# CAN1.net
KiCad netlist of a schematic drawn in Altium Designer
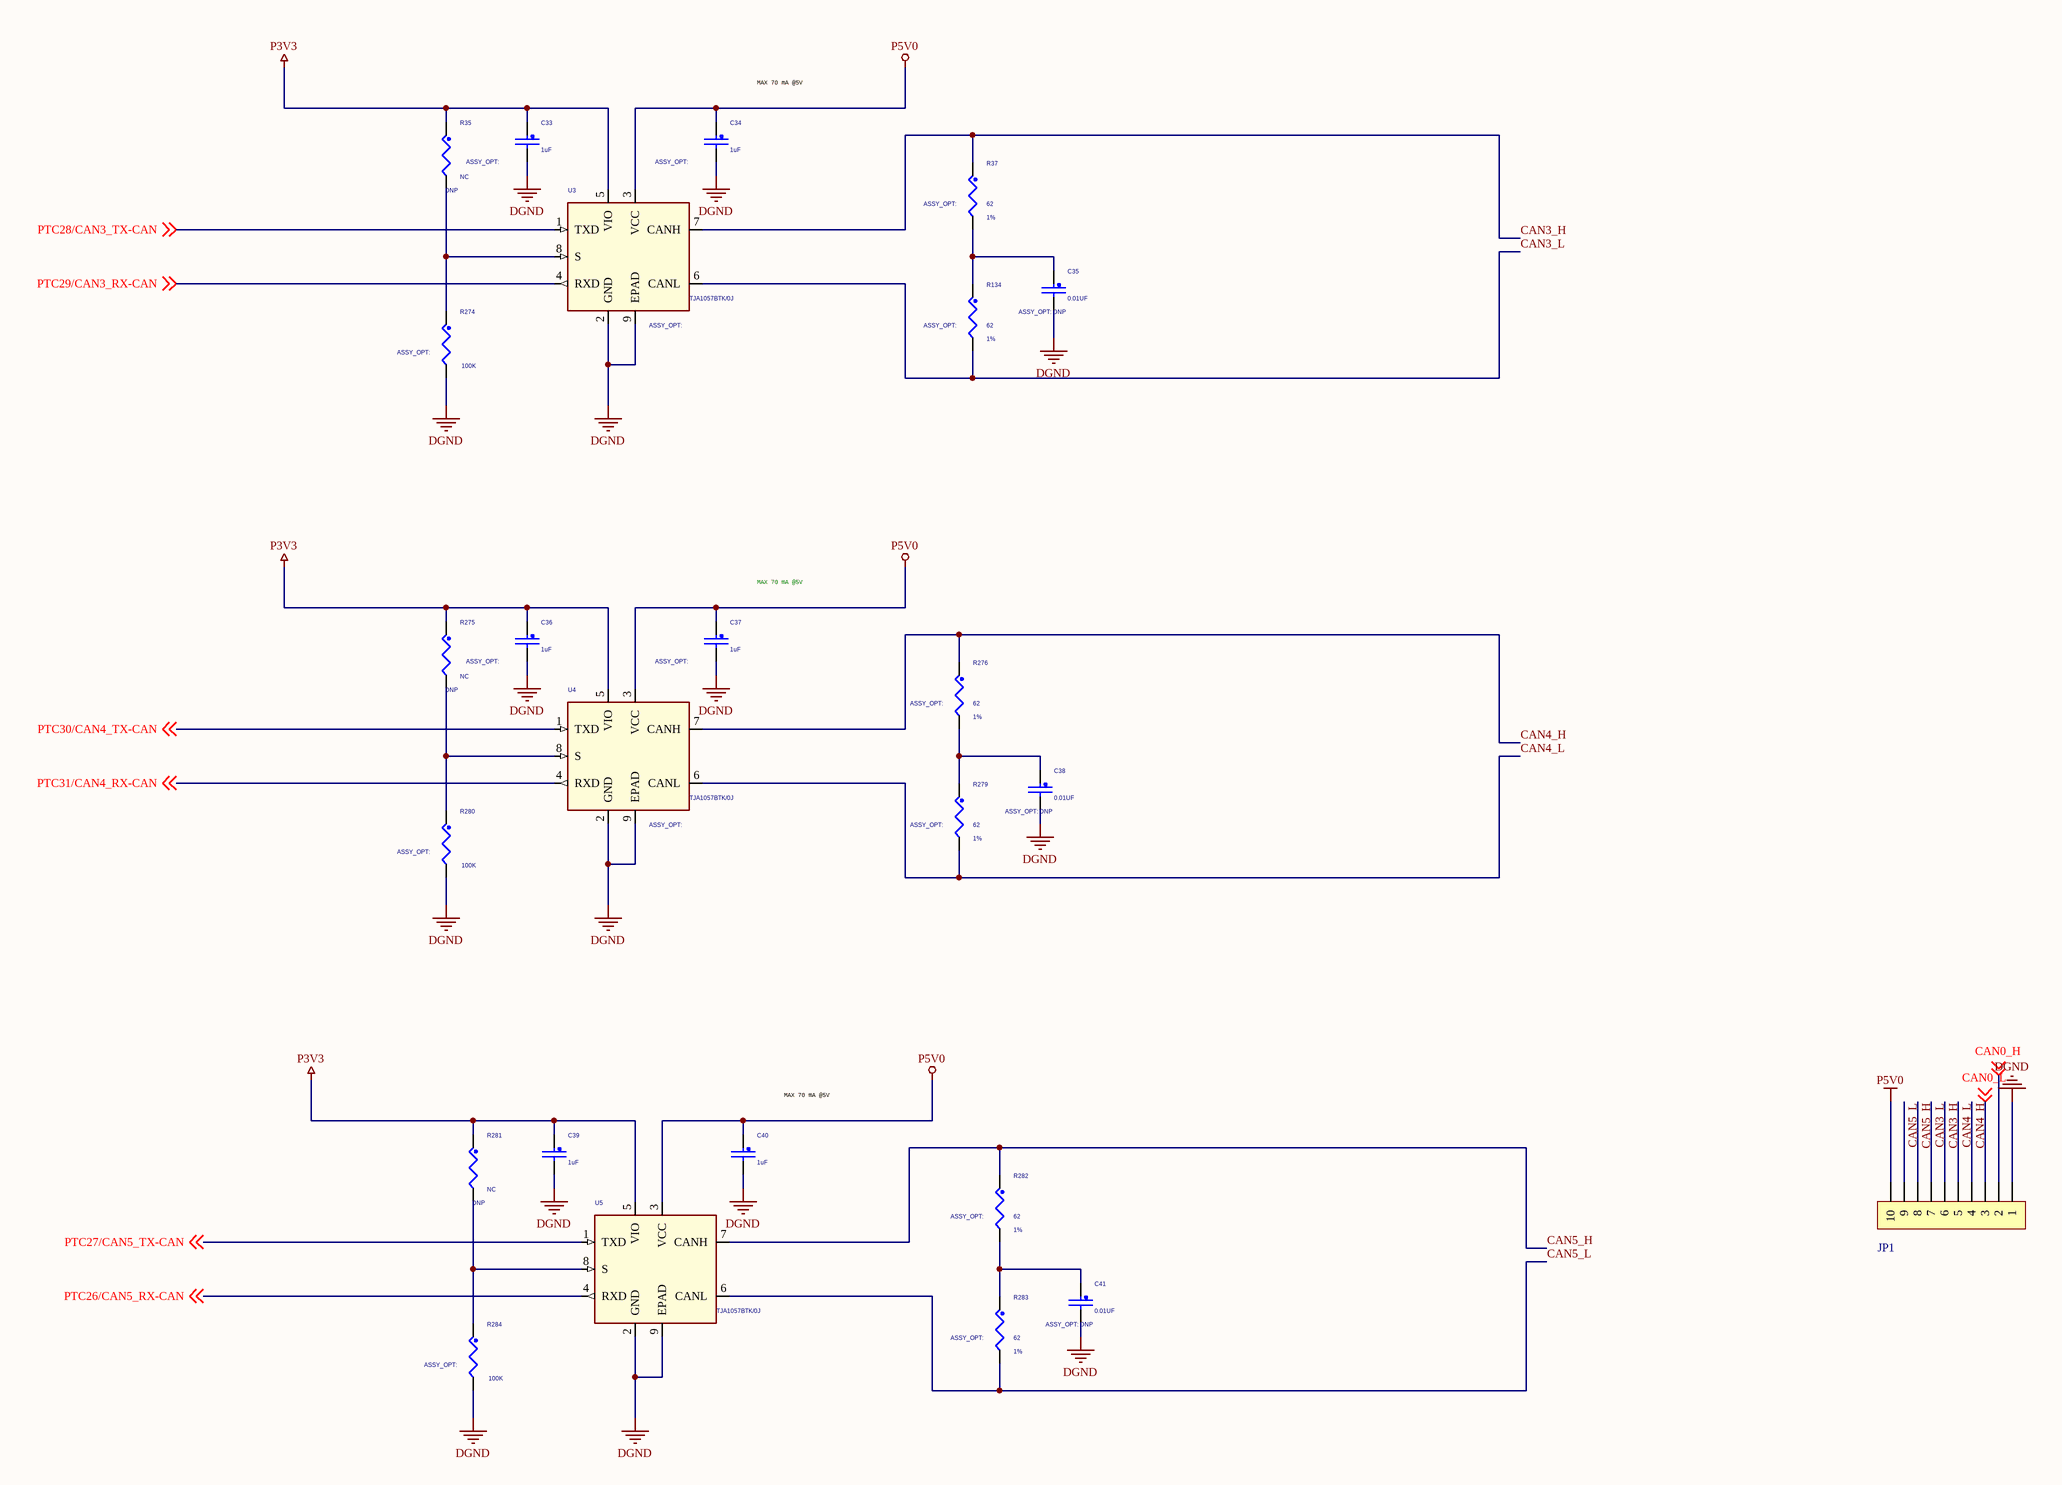
[diagram p0: CAN1.SchDoc]

(export (version "E")
  (design (tool "Eeschema 10.0.6"))
  (components
    (comp (ref "C33")
      (value "1uF")
      (footprint "CC0402_25")
      (description "CAP CER 1.0uF 16V 10% X6S 0402")
      (fields (field (name "VOLTAGE") "16V") (field (name "TOLERANCE") "10%"))
      (libsource (lib "*") (part "CAP_NP"))
    )
    (comp (ref "C34")
      (value "1uF")
      (footprint "CC0402_25")
      (description "CAP CER 1.0uF 16V 10% X6S 0402")
      (fields (field (name "VOLTAGE") "16V") (field (name "TOLERANCE") "10%"))
      (libsource (lib "*") (part "CAP_NP"))
    )
    (comp (ref "C35")
      (value "0.01UF")
      (footprint "CC0402_25")
      (description "CAP CER 0.01UF 50V 10% X7R 0402")
      (fields (field (name "ASSY_OPT") "DNP") (field (name "TOLERANCE") "10%"))
      (libsource (lib "*") (part "CAP_NP"))
    )
    (comp (ref "C36")
      (value "1uF")
      (footprint "CC0402_25")
      (description "CAP CER 1.0uF 16V 10% X6S 0402")
      (fields (field (name "TOLERANCE") "10%") (field (name "VOLTAGE") "16V"))
      (libsource (lib "*") (part "CAP_NP"))
    )
    (comp (ref "C37")
      (value "1uF")
      (footprint "CC0402_25")
      (description "CAP CER 1.0uF 16V 10% X6S 0402")
      (fields (field (name "TOLERANCE") "10%") (field (name "VOLTAGE") "16V"))
      (libsource (lib "*") (part "CAP_NP"))
    )
    (comp (ref "C38")
      (value "0.01UF")
      (footprint "CC0402_25")
      (description "CAP CER 0.01UF 50V 10% X7R 0402")
      (fields (field (name "ASSY_OPT") "DNP") (field (name "TOLERANCE") "10%"))
      (libsource (lib "*") (part "CAP_NP"))
    )
    (comp (ref "C39")
      (value "1uF")
      (footprint "CC0402_25")
      (description "CAP CER 1.0uF 16V 10% X6S 0402")
      (fields (field (name "VOLTAGE") "16V") (field (name "TOLERANCE") "10%"))
      (libsource (lib "*") (part "CAP_NP"))
    )
    (comp (ref "C40")
      (value "1uF")
      (footprint "CC0402_25")
      (description "CAP CER 1.0uF 16V 10% X6S 0402")
      (fields (field (name "TOLERANCE") "10%") (field (name "VOLTAGE") "16V"))
      (libsource (lib "*") (part "CAP_NP"))
    )
    (comp (ref "C41")
      (value "0.01UF")
      (footprint "CC0402_25")
      (description "CAP CER 0.01UF 50V 10% X7R 0402")
      (fields (field (name "ASSY_OPT") "DNP") (field (name "TOLERANCE") "10%"))
      (libsource (lib "*") (part "CAP_NP"))
    )
    (comp (ref "JP1")
      (value "HDR-1X10")
      (footprint "KF128-3.81-10P")
      (description "10P接插件")
      (libsource (lib "4.8   - 接插件-脚距3.81") (part "Header 10"))
    )
    (comp (ref "R35")
      (value "NC")
      (footprint "RC0402_25")
      (description "RES MF 10K 1/16W 5% 0402")
      (fields (field (name "ASSY_OPT") "DNP") (field (name "TOLERANCE") "5%"))
      (libsource (lib "*") (part "RES"))
    )
    (comp (ref "R37")
      (value "62")
      (footprint "RC0805_OV")
      (description "RES MF 62 OHM 1/4W 1% AEC-Q200 0805")
      (fields (field (name "TOLERANCE") "1%"))
      (libsource (lib "*") (part "RES"))
    )
    (comp (ref "R134")
      (value "62")
      (footprint "RC0805_OV")
      (description "RES MF 62 OHM 1/4W 1% AEC-Q200 0805")
      (fields (field (name "TOLERANCE") "1%"))
      (libsource (lib "*") (part "RES"))
    )
    (comp (ref "R274")
      (value "100K")
      (footprint "RC0402_25")
      (description "RES MF 100K 1/16W 1% 0402")
      (fields (field (name "TOLERANCE") "1%"))
      (libsource (lib "*") (part "RES"))
    )
    (comp (ref "R275")
      (value "NC")
      (footprint "RC0402_25")
      (description "RES MF 10K 1/16W 5% 0402")
      (fields (field (name "ASSY_OPT") "DNP") (field (name "TOLERANCE") "5%"))
      (libsource (lib "*") (part "RES"))
    )
    (comp (ref "R276")
      (value "62")
      (footprint "RC0805_OV")
      (description "RES MF 62 OHM 1/4W 1% AEC-Q200 0805")
      (fields (field (name "TOLERANCE") "1%"))
      (libsource (lib "*") (part "RES"))
    )
    (comp (ref "R279")
      (value "62")
      (footprint "RC0805_OV")
      (description "RES MF 62 OHM 1/4W 1% AEC-Q200 0805")
      (fields (field (name "TOLERANCE") "1%"))
      (libsource (lib "*") (part "RES"))
    )
    (comp (ref "R280")
      (value "100K")
      (footprint "RC0402_25")
      (description "RES MF 100K 1/16W 1% 0402")
      (fields (field (name "TOLERANCE") "1%"))
      (libsource (lib "*") (part "RES"))
    )
    (comp (ref "R281")
      (value "NC")
      (footprint "RC0402_25")
      (description "RES MF 10K 1/16W 5% 0402")
      (fields (field (name "ASSY_OPT") "DNP") (field (name "TOLERANCE") "5%"))
      (libsource (lib "*") (part "RES"))
    )
    (comp (ref "R282")
      (value "62")
      (footprint "RC0805_OV")
      (description "RES MF 62 OHM 1/4W 1% AEC-Q200 0805")
      (fields (field (name "TOLERANCE") "1%"))
      (libsource (lib "*") (part "RES"))
    )
    (comp (ref "R283")
      (value "62")
      (footprint "RC0805_OV")
      (description "RES MF 62 OHM 1/4W 1% AEC-Q200 0805")
      (fields (field (name "TOLERANCE") "1%"))
      (libsource (lib "*") (part "RES"))
    )
    (comp (ref "R284")
      (value "100K")
      (footprint "RC0402_25")
      (description "RES MF 100K 1/16W 1% 0402")
      (fields (field (name "TOLERANCE") "1%"))
      (libsource (lib "*") (part "RES"))
    )
    (comp (ref "U3")
      (value "TJA1057BTK")
      (footprint "son8_0p65_3p15x3p15")
      (description "IC XCVR CAN 4.5-5.5V AEC-Q100 HVSON8")
      (fields (field (name "MFG_PN01") "TJA1057BTK/0J"))
      (libsource (lib "*") (part "TJA1051TK_3_HVSON8"))
    )
    (comp (ref "U4")
      (value "TJA1057BTK")
      (footprint "son8_0p65_3p15x3p15")
      (description "IC XCVR CAN 4.5-5.5V AEC-Q100 HVSON8")
      (fields (field (name "MFG_PN01") "TJA1057BTK/0J"))
      (libsource (lib "*") (part "TJA1051TK_3_HVSON8"))
    )
    (comp (ref "U5")
      (value "TJA1057BTK")
      (footprint "son8_0p65_3p15x3p15")
      (description "IC XCVR CAN 4.5-5.5V AEC-Q100 HVSON8")
      (fields (field (name "MFG_PN01") "TJA1057BTK/0J"))
      (libsource (lib "*") (part "TJA1051TK_3_HVSON8"))
    )
  )
  (nets
    (net (code "1") (name "/CAN3_H") (class "Default")
      (node (ref "JP1") (pin "6") (pinfunction "6_6") (pintype "passive"))
      (node (ref "R37") (pin "1") (pinfunction "1_1") (pintype "passive"))
      (node (ref "U3") (pin "7") (pinfunction "CANH_7") (pintype "bidirectional"))
    )
    (net (code "2") (name "/CAN3_L") (class "Default")
      (node (ref "JP1") (pin "7") (pinfunction "7_7") (pintype "passive"))
      (node (ref "R134") (pin "2") (pinfunction "2_2") (pintype "passive"))
      (node (ref "U3") (pin "6") (pinfunction "CANL_6") (pintype "bidirectional"))
    )
    (net (code "3") (name "/CAN4_H") (class "Default")
      (node (ref "JP1") (pin "4") (pinfunction "4_4") (pintype "passive"))
      (node (ref "R276") (pin "1") (pinfunction "1_1") (pintype "passive"))
      (node (ref "U4") (pin "7") (pinfunction "CANH_7") (pintype "bidirectional"))
    )
    (net (code "4") (name "/CAN4_L") (class "Default")
      (node (ref "JP1") (pin "5") (pinfunction "5_5") (pintype "passive"))
      (node (ref "R279") (pin "2") (pinfunction "2_2") (pintype "passive"))
      (node (ref "U4") (pin "6") (pinfunction "CANL_6") (pintype "bidirectional"))
    )
    (net (code "5") (name "/CAN5_H") (class "Default")
      (node (ref "JP1") (pin "8") (pinfunction "8_8") (pintype "passive"))
      (node (ref "R282") (pin "1") (pinfunction "1_1") (pintype "passive"))
      (node (ref "U5") (pin "7") (pinfunction "CANH_7") (pintype "bidirectional"))
    )
    (net (code "6") (name "/CAN5_L") (class "Default")
      (node (ref "JP1") (pin "9") (pinfunction "9_9") (pintype "passive"))
      (node (ref "R283") (pin "2") (pinfunction "2_2") (pintype "passive"))
      (node (ref "U5") (pin "6") (pinfunction "CANL_6") (pintype "bidirectional"))
    )
    (net (code "7") (name "CAN0_H") (class "Default")
      (node (ref "JP1") (pin "2") (pinfunction "2_2") (pintype "passive"))
    )
    (net (code "8") (name "CAN0_L") (class "Default")
      (node (ref "JP1") (pin "3") (pinfunction "3_3") (pintype "passive"))
    )
    (net (code "9") (name "DGND") (class "Default")
      (node (ref "C33") (pin "2") (pinfunction "2_2") (pintype "passive"))
      (node (ref "C34") (pin "2") (pinfunction "2_2") (pintype "passive"))
      (node (ref "C35") (pin "2") (pinfunction "2_2") (pintype "passive"))
      (node (ref "C36") (pin "2") (pinfunction "2_2") (pintype "passive"))
      (node (ref "C37") (pin "2") (pinfunction "2_2") (pintype "passive"))
      (node (ref "C38") (pin "2") (pinfunction "2_2") (pintype "passive"))
      (node (ref "C39") (pin "2") (pinfunction "2_2") (pintype "passive"))
      (node (ref "C40") (pin "2") (pinfunction "2_2") (pintype "passive"))
      (node (ref "C41") (pin "2") (pinfunction "2_2") (pintype "passive"))
      (node (ref "JP1") (pin "1") (pinfunction "1_1") (pintype "passive"))
      (node (ref "R274") (pin "2") (pinfunction "2_2") (pintype "passive"))
      (node (ref "R280") (pin "2") (pinfunction "2_2") (pintype "passive"))
      (node (ref "R284") (pin "2") (pinfunction "2_2") (pintype "passive"))
      (node (ref "U3") (pin "2") (pinfunction "GND_2") (pintype "power_in"))
      (node (ref "U3") (pin "9") (pinfunction "EPAD_9") (pintype "power_in"))
      (node (ref "U4") (pin "2") (pinfunction "GND_2") (pintype "power_in"))
      (node (ref "U4") (pin "9") (pinfunction "EPAD_9") (pintype "power_in"))
      (node (ref "U5") (pin "2") (pinfunction "GND_2") (pintype "power_in"))
      (node (ref "U5") (pin "9") (pinfunction "EPAD_9") (pintype "power_in"))
    )
    (net (code "10") (name "Net-(C35-Pad1)") (class "Default")
      (node (ref "C35") (pin "1") (pinfunction "1_1") (pintype "passive"))
      (node (ref "R134") (pin "1") (pinfunction "1_1") (pintype "passive"))
      (node (ref "R37") (pin "2") (pinfunction "2_2") (pintype "passive"))
    )
    (net (code "11") (name "Net-(C38-Pad1)") (class "Default")
      (node (ref "C38") (pin "1") (pinfunction "1_1") (pintype "passive"))
      (node (ref "R276") (pin "2") (pinfunction "2_2") (pintype "passive"))
      (node (ref "R279") (pin "1") (pinfunction "1_1") (pintype "passive"))
    )
    (net (code "12") (name "Net-(C41-Pad1)") (class "Default")
      (node (ref "C41") (pin "1") (pinfunction "1_1") (pintype "passive"))
      (node (ref "R282") (pin "2") (pinfunction "2_2") (pintype "passive"))
      (node (ref "R283") (pin "1") (pinfunction "1_1") (pintype "passive"))
    )
    (net (code "13") (name "Net-(U3-S)") (class "Default")
      (node (ref "R274") (pin "1") (pinfunction "1_1") (pintype "passive"))
      (node (ref "R35") (pin "2") (pinfunction "2_2") (pintype "passive"))
      (node (ref "U3") (pin "8") (pinfunction "S_8") (pintype "input"))
    )
    (net (code "14") (name "Net-(U4-S)") (class "Default")
      (node (ref "R275") (pin "2") (pinfunction "2_2") (pintype "passive"))
      (node (ref "R280") (pin "1") (pinfunction "1_1") (pintype "passive"))
      (node (ref "U4") (pin "8") (pinfunction "S_8") (pintype "input"))
    )
    (net (code "15") (name "Net-(U5-S)") (class "Default")
      (node (ref "R281") (pin "2") (pinfunction "2_2") (pintype "passive"))
      (node (ref "R284") (pin "1") (pinfunction "1_1") (pintype "passive"))
      (node (ref "U5") (pin "8") (pinfunction "S_8") (pintype "input"))
    )
    (net (code "16") (name "P3V3") (class "Default")
      (node (ref "C33") (pin "1") (pinfunction "1_1") (pintype "passive"))
      (node (ref "C36") (pin "1") (pinfunction "1_1") (pintype "passive"))
      (node (ref "C39") (pin "1") (pinfunction "1_1") (pintype "passive"))
      (node (ref "R275") (pin "1") (pinfunction "1_1") (pintype "passive"))
      (node (ref "R281") (pin "1") (pinfunction "1_1") (pintype "passive"))
      (node (ref "R35") (pin "1") (pinfunction "1_1") (pintype "passive"))
      (node (ref "U3") (pin "5") (pinfunction "VIO_5") (pintype "power_in"))
      (node (ref "U4") (pin "5") (pinfunction "VIO_5") (pintype "power_in"))
      (node (ref "U5") (pin "5") (pinfunction "VIO_5") (pintype "power_in"))
    )
    (net (code "17") (name "P5V0") (class "Default")
      (node (ref "C34") (pin "1") (pinfunction "1_1") (pintype "passive"))
      (node (ref "C37") (pin "1") (pinfunction "1_1") (pintype "passive"))
      (node (ref "C40") (pin "1") (pinfunction "1_1") (pintype "passive"))
      (node (ref "JP1") (pin "10") (pinfunction "10_10") (pintype "passive"))
      (node (ref "U3") (pin "3") (pinfunction "VCC_3") (pintype "power_in"))
      (node (ref "U4") (pin "3") (pinfunction "VCC_3") (pintype "power_in"))
      (node (ref "U5") (pin "3") (pinfunction "VCC_3") (pintype "power_in"))
    )
    (net (code "18") (name "PTC26{slash}CAN5_RX-CAN") (class "Default")
      (node (ref "U5") (pin "4") (pinfunction "RXD_4") (pintype "output"))
    )
    (net (code "19") (name "PTC27{slash}CAN5_TX-CAN") (class "Default")
      (node (ref "U5") (pin "1") (pinfunction "TXD_1") (pintype "input"))
    )
    (net (code "20") (name "PTC28{slash}CAN3_TX-CAN") (class "Default")
      (node (ref "U3") (pin "1") (pinfunction "TXD_1") (pintype "input"))
    )
    (net (code "21") (name "PTC29{slash}CAN3_RX-CAN") (class "Default")
      (node (ref "U3") (pin "4") (pinfunction "RXD_4") (pintype "output"))
    )
    (net (code "22") (name "PTC30{slash}CAN4_TX-CAN") (class "Default")
      (node (ref "U4") (pin "1") (pinfunction "TXD_1") (pintype "input"))
    )
    (net (code "23") (name "PTC31{slash}CAN4_RX-CAN") (class "Default")
      (node (ref "U4") (pin "4") (pinfunction "RXD_4") (pintype "output"))
    )
  )
)
